# Sheet1.net
KiCad netlist of a schematic drawn in Altium Designer
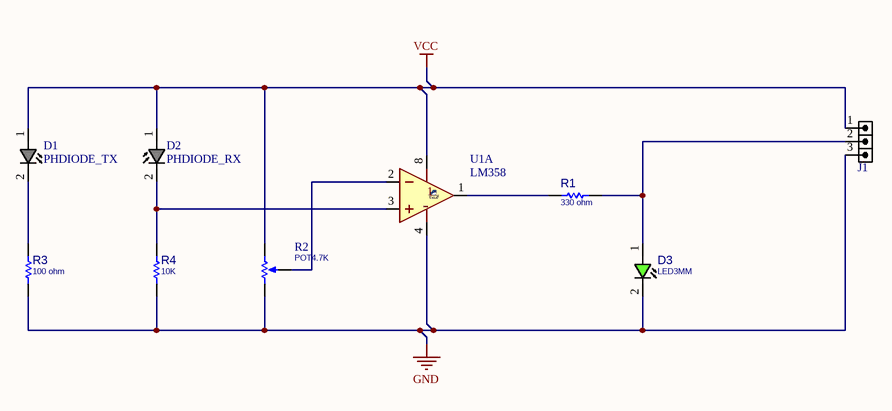
[diagram p0: Sheet1.SchDoc]

(export (version "E")
  (design (tool "Eeschema 10.0.6"))
  (components
    (comp (ref "D1")
      (value "PHDIODE_TX")
      (footprint "LED3MM")
      (description "LED, Infrared Transmitter")
      (libsource (lib "sensor_light") (part "PHDIODE_TX"))
    )
    (comp (ref "D2")
      (value "PHDIODE_RX")
      (footprint "LED3MM")
      (description "LED, Infrared Receiver")
      (libsource (lib "sensor_light") (part "PHDIODE_RX"))
    )
    (comp (ref "D3")
      (value "LED3MM")
      (footprint "LED3MM")
      (description "LED, THD, 3MM, GREEN")
      (fields (field (name "MANF") "MANF") (field (name "MANF_P#") "MANF_PART#"))
      (libsource (lib "led(diode)") (part "LED_THD_3MM"))
    )
    (comp (ref "J1")
      (value "HDRM3")
      (footprint "HDRR_M_1X3")
      (description "CONN, HEADER, RightAngle, Male, pitch: 2.54mm, 3POS")
      (libsource (lib "conn_header_2.54mm_ra") (part "HDRR_M_1X3"))
    )
    (comp (ref "R1")
      (value "330 ohm")
      (footprint "R025W_AX04")
      (description "RESISTOR, THD")
      (fields (field (name "MANF_P#") "RK73H1ETTP4701F") (field (name "MANF") "KOA SPEER"))
      (libsource (lib "passive_thd") (part "RES_THD"))
    )
    (comp (ref "R2")
      (value "POT4.7K")
      (footprint "POT_PIHER15MM")
      (description "RESISTOR, THD, Potentiometer, PT-15 15mm")
      (fields (field (name "MANF") "PIHER") (field (name "MANF_P#") "PT15NV15"))
      (libsource (lib "resistor_pot_trimmer") (part "RES_THD_POT_PT15"))
    )
    (comp (ref "R3")
      (value "100 ohm")
      (footprint "R025W_AX04")
      (description "RESISTOR, THD")
      (fields (field (name "MANF_P#") "RK73H1ETTP4701F") (field (name "MANF") "KOA SPEER"))
      (libsource (lib "passive_thd") (part "RES_THD"))
    )
    (comp (ref "R4")
      (value "10K")
      (footprint "R025W_AX04")
      (description "RESISTOR, THD")
      (fields (field (name "MANF_P#") "RK73H1ETTP4701F") (field (name "MANF") "KOA SPEER"))
      (libsource (lib "passive_thd") (part "RES_THD"))
    )
    (comp (ref "U1")
      (value "LM358")
      (footprint "DIP_8")
      (description "AMP, Dual, Low-Power")
      (fields (field (name "MANF") "Texas Instruments, Fairchild") (field (name "MANF_P#") "LM358AN"))
      (libsource (lib "amp") (part "LM358_DIP8"))
    )
  )
  (nets
    (net (code "1") (name "GND") (class "Default")
      (node (ref "D3") (pin "2") (pinfunction "CATHODE_2") (pintype "passive"))
      (node (ref "J1") (pin "3") (pinfunction "3_3") (pintype "passive"))
      (node (ref "R2") (pin "1") (pinfunction "TOP_1") (pintype "passive"))
      (node (ref "R3") (pin "1") (pinfunction "1_1") (pintype "passive"))
      (node (ref "R4") (pin "1") (pinfunction "1_1") (pintype "passive"))
      (node (ref "U1") (pin "4") (pinfunction "V-_4") (pintype "passive"))
    )
    (net (code "2") (name "Net-(D1-CATHODE)") (class "Default")
      (node (ref "D1") (pin "2") (pinfunction "CATHODE_2") (pintype "passive"))
      (node (ref "R3") (pin "2") (pinfunction "2_2") (pintype "passive"))
    )
    (net (code "3") (name "Net-(D2-CATHODE)") (class "Default")
      (node (ref "D2") (pin "2") (pinfunction "CATHODE_2") (pintype "passive"))
      (node (ref "R4") (pin "2") (pinfunction "2_2") (pintype "passive"))
      (node (ref "U1") (pin "3") (pinfunction "IN+_3") (pintype "passive"))
    )
    (net (code "4") (name "Net-(D3-ANODE)") (class "Default")
      (node (ref "D3") (pin "1") (pinfunction "ANODE_1") (pintype "passive"))
      (node (ref "J1") (pin "2") (pinfunction "2_2") (pintype "passive"))
      (node (ref "R1") (pin "1") (pinfunction "1_1") (pintype "passive"))
    )
    (net (code "5") (name "Net-(R2-TAP)") (class "Default")
      (node (ref "R2") (pin "2") (pinfunction "TAP_2") (pintype "passive"))
      (node (ref "U1") (pin "2") (pinfunction "IN-_2") (pintype "passive"))
    )
    (net (code "6") (name "Net-(U1A-OUT)") (class "Default")
      (node (ref "R1") (pin "2") (pinfunction "2_2") (pintype "passive"))
      (node (ref "U1") (pin "1") (pinfunction "OUT_1") (pintype "passive"))
    )
    (net (code "7") (name "VCC") (class "Default")
      (node (ref "D1") (pin "1") (pinfunction "ANODE_1") (pintype "passive"))
      (node (ref "D2") (pin "1") (pinfunction "ANODE_1") (pintype "passive"))
      (node (ref "J1") (pin "1") (pinfunction "1_1") (pintype "passive"))
      (node (ref "R2") (pin "3") (pinfunction "BOT_3") (pintype "passive"))
      (node (ref "U1") (pin "8") (pinfunction "V+_8") (pintype "passive"))
    )
  )
)
